# Page_Tete.net
KiCad netlist of a schematic drawn in Altium Designer
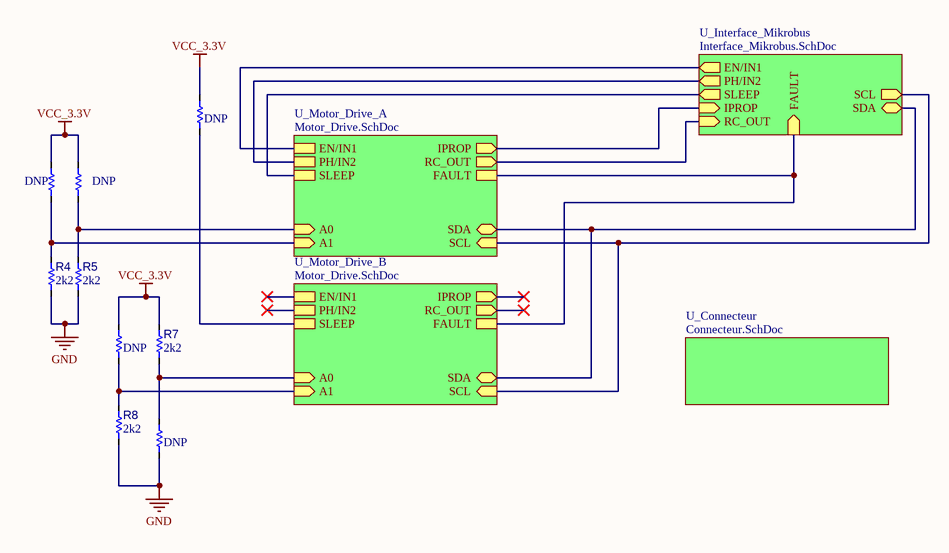
[diagram p0: Page_Tete.SchDoc]

(export (version "E")
  (design (tool "Eeschema 10.0.6"))
  (components
    (comp (ref "R1")
      (value "DNP")
      (footprint "R_1005[0402]")
      (description "Resistor type 1")
      (fields (field (name "TOLERANCE") "1%") (field (name "Comment") "Res 2k2 1% 0402"))
      (libsource (lib "243-436-MikoBus-DrvMot") (part "resistor"))
    )
    (comp (ref "R2")
      (value "DNP")
      (footprint "R_1005[0402]")
      (description "Resistor type 1")
      (fields (field (name "TOLERANCE") "1%") (field (name "Comment") "Res 2k2 1% 0402"))
      (libsource (lib "243-436-MikoBus-DrvMot") (part "resistor"))
    )
    (comp (ref "R3")
      (value "DNP")
      (footprint "R_1005[0402]")
      (description "Resistor type 1")
      (fields (field (name "TOLERANCE") "1%") (field (name "Comment") "Res 2k2 1% 0402"))
      (libsource (lib "243-436-MikoBus-DrvMot") (part "resistor"))
    )
    (comp (ref "R4")
      (value "2k2")
      (footprint "R_1005[0402]")
      (description "Resistor type 1")
      (fields (field (name "TOLERANCE") "1%") (field (name "Comment") "Res 2k2 1% 0402"))
      (libsource (lib "243-436-MikoBus-DrvMot") (part "resistor"))
    )
    (comp (ref "R5")
      (value "2k2")
      (footprint "R_1005[0402]")
      (description "Resistor type 1")
      (fields (field (name "TOLERANCE") "1%") (field (name "Comment") "Res 2k2 1% 0402"))
      (libsource (lib "243-436-MikoBus-DrvMot") (part "resistor"))
    )
    (comp (ref "R6")
      (value "DNP")
      (footprint "R_1005[0402]")
      (description "Resistor type 1")
      (fields (field (name "TOLERANCE") "1%") (field (name "Comment") "Res 2k2 1% 0402"))
      (libsource (lib "243-436-MikoBus-DrvMot") (part "resistor"))
    )
    (comp (ref "R7")
      (value "2k2")
      (footprint "R_1005[0402]")
      (description "Resistor type 1")
      (fields (field (name "TOLERANCE") "1%") (field (name "Comment") "Res 2k2 1% 0402"))
      (libsource (lib "243-436-MikoBus-DrvMot") (part "resistor"))
    )
    (comp (ref "R8")
      (value "2k2")
      (footprint "R_1005[0402]")
      (description "Resistor type 1")
      (fields (field (name "TOLERANCE") "1%") (field (name "Comment") "Res 2k2 1% 0402"))
      (libsource (lib "243-436-MikoBus-DrvMot") (part "resistor"))
    )
    (comp (ref "R9")
      (value "DNP")
      (footprint "R_1005[0402]")
      (description "Resistor type 1")
      (fields (field (name "TOLERANCE") "1%") (field (name "Comment") "Res 2k2 1% 0402"))
      (libsource (lib "243-436-MikoBus-DrvMot") (part "resistor"))
    )
  )
  (nets
    (net (code "1") (name "/A0") (class "Default")
      (node (ref "R3") (pin "1") (pinfunction "1_1") (pintype "passive"))
      (node (ref "R5") (pin "2") (pinfunction "2_2") (pintype "passive"))
    )
    (net (code "2") (name "/A0_1") (class "Default")
      (node (ref "R7") (pin "1") (pinfunction "1_1") (pintype "passive"))
      (node (ref "R9") (pin "2") (pinfunction "2_2") (pintype "passive"))
    )
    (net (code "3") (name "/A1") (class "Default")
      (node (ref "R2") (pin "1") (pinfunction "1_1") (pintype "passive"))
      (node (ref "R4") (pin "2") (pinfunction "2_2") (pintype "passive"))
    )
    (net (code "4") (name "/A1_1") (class "Default")
      (node (ref "R6") (pin "1") (pinfunction "1_1") (pintype "passive"))
      (node (ref "R8") (pin "2") (pinfunction "2_2") (pintype "passive"))
    )
    (net (code "17") (name "/SLEEP_1") (class "Default")
      (node (ref "R1") (pin "1") (pinfunction "1_1") (pintype "passive"))
    )
    (net (code "18") (name "GND") (class "Default")
      (node (ref "R4") (pin "1") (pinfunction "1_1") (pintype "passive"))
      (node (ref "R5") (pin "1") (pinfunction "1_1") (pintype "passive"))
      (node (ref "R8") (pin "1") (pinfunction "1_1") (pintype "passive"))
      (node (ref "R9") (pin "1") (pinfunction "1_1") (pintype "passive"))
    )
    (net (code "19") (name "VCC_3.3V") (class "Default")
      (node (ref "R1") (pin "2") (pinfunction "2_2") (pintype "passive"))
      (node (ref "R2") (pin "2") (pinfunction "2_2") (pintype "passive"))
      (node (ref "R3") (pin "2") (pinfunction "2_2") (pintype "passive"))
      (node (ref "R6") (pin "2") (pinfunction "2_2") (pintype "passive"))
      (node (ref "R7") (pin "2") (pinfunction "2_2") (pintype "passive"))
    )
  )
)
